# Strain_sensor.net
KiCad netlist of a schematic drawn in Altium Designer
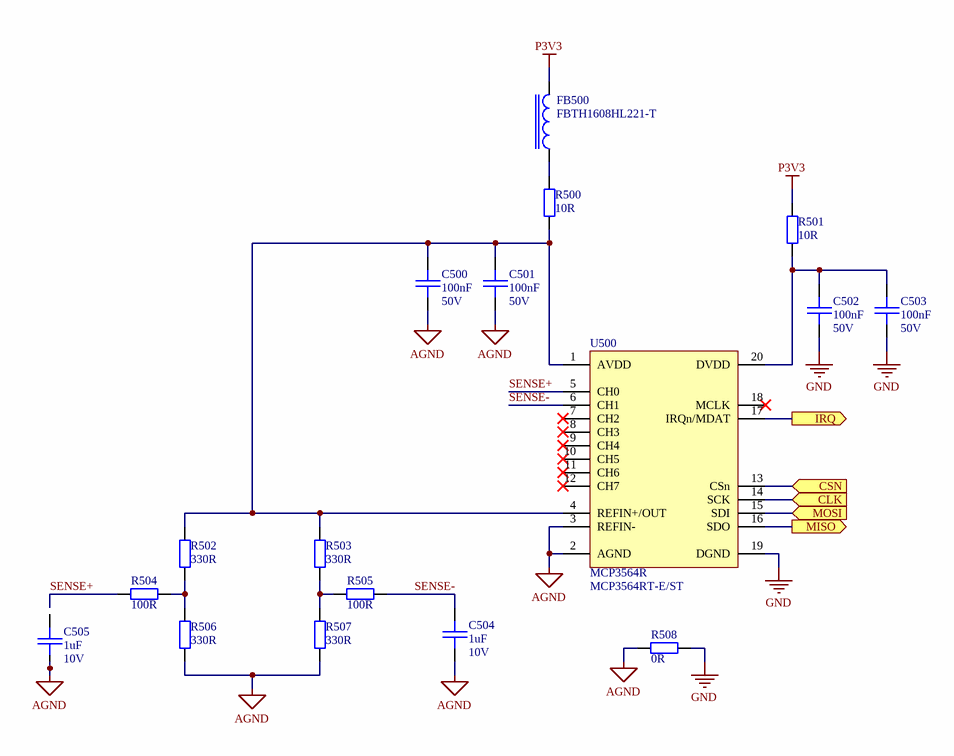
[diagram p0: Strain_sensor.SchDoc]

(export (version "E")
  (design (tool "Eeschema 10.0.6"))
  (components
    (comp (ref "C500")
      (value "100nF")
      (footprint "C0402")
      (description "General purpose ceramic capacitor")
      (fields
        (field (name "VOLTAGE") "50V")
        (field (name "MANUFACTURER") "Murata Electronics")
        (field (name "MANUFACTURER PART NO") "GRT155R71H104KE01D")
      )
      (libsource (lib "Moonlight_Library") (part "CAP"))
    )
    (comp (ref "C501")
      (value "100nF")
      (footprint "C0402")
      (description "General purpose ceramic capacitor")
      (fields
        (field (name "VOLTAGE") "50V")
        (field (name "MANUFACTURER") "Murata Electronics")
        (field (name "MANUFACTURER PART NO") "GRT155R71H104KE01D")
      )
      (libsource (lib "Moonlight_Library") (part "CAP"))
    )
    (comp (ref "C502")
      (value "100nF")
      (footprint "C0402")
      (description "General purpose ceramic capacitor")
      (fields
        (field (name "VOLTAGE") "50V")
        (field (name "MANUFACTURER") "Murata Electronics")
        (field (name "MANUFACTURER PART NO") "GRT155R71H104KE01D")
      )
      (libsource (lib "Moonlight_Library") (part "CAP"))
    )
    (comp (ref "C503")
      (value "100nF")
      (footprint "C0402")
      (description "General purpose ceramic capacitor")
      (fields
        (field (name "VOLTAGE") "50V")
        (field (name "MANUFACTURER") "Murata Electronics")
        (field (name "MANUFACTURER PART NO") "GRT155R71H104KE01D")
      )
      (libsource (lib "Moonlight_Library") (part "CAP"))
    )
    (comp (ref "C504")
      (value "1uF")
      (footprint "C0402")
      (description "General purpose ceramic capacitor")
      (fields
        (field (name "VOLTAGE") "10V")
        (field (name "MANUFACTURER") "Murata Electronics")
        (field (name "MANUFACTURER PART NO") "GRT155R61A105KE01D")
      )
      (libsource (lib "Moonlight_Library") (part "CAP"))
    )
    (comp (ref "C505")
      (value "1uF")
      (footprint "C0402")
      (description "General purpose ceramic capacitor")
      (fields
        (field (name "VOLTAGE") "10V")
        (field (name "MANUFACTURER") "Murata Electronics")
        (field (name "MANUFACTURER PART NO") "GRT155R61A105KE01D")
      )
      (libsource (lib "Moonlight_Library") (part "CAP"))
    )
    (comp (ref "FB500")
      (value "FBEAD")
      (footprint "0603_IND")
      (description "Ferrite bead")
      (fields
        (field (name "MANUFACTURER") "Taiyo Yuden")
        (field (name "MANUFACTURER PART NO") "FBTH1608HL221-T")
      )
      (libsource (lib "Moonlight_Library") (part "FBEAD"))
    )
    (comp (ref "R500")
      (value "10R")
      (footprint "R0603")
      (description "General purpose automotive thick film resistor")
      (fields
        (field (name "MANUFACTURER") "Vishay Dale")
        (field (name "MANUFACTURER PART NO") "CRCW060310R0JNEA")
      )
      (libsource (lib "Moonlight_Library") (part "RES"))
    )
    (comp (ref "R501")
      (value "10R")
      (footprint "R0603")
      (description "General purpose automotive thick film resistor")
      (fields
        (field (name "MANUFACTURER") "Vishay Dale")
        (field (name "MANUFACTURER PART NO") "CRCW060310R0JNEA")
      )
      (libsource (lib "Moonlight_Library") (part "RES"))
    )
    (comp (ref "R502")
      (value "330R")
      (footprint "R2512")
      (description "General purpose automotive thick film resistor")
      (fields
        (field (name "MANUFACTURER") "Vishay Dale")
        (field (name "MANUFACTURER PART NO") "CRCW2512330RJNEG")
      )
      (libsource (lib "Moonlight_Library") (part "RES"))
    )
    (comp (ref "R503")
      (value "330R")
      (footprint "R2512")
      (description "General purpose automotive thick film resistor")
      (fields
        (field (name "MANUFACTURER") "Vishay Dale")
        (field (name "MANUFACTURER PART NO") "CRCW2512330RJNEG")
      )
      (libsource (lib "Moonlight_Library") (part "RES"))
    )
    (comp (ref "R504")
      (value "100R")
      (footprint "R0603")
      (description "General purpose automotive thick film resistor")
      (fields
        (field (name "MANUFACTURER") "Vishay Dale")
        (field (name "MANUFACTURER PART NO") "CRCW0603100RJNEA")
      )
      (libsource (lib "") (part "RES_1"))
    )
    (comp (ref "R505")
      (value "100R")
      (footprint "R0603")
      (description "General purpose automotive thick film resistor")
      (fields
        (field (name "MANUFACTURER") "Vishay Dale")
        (field (name "MANUFACTURER PART NO") "CRCW0603100RJNEA")
      )
      (libsource (lib "") (part "RES_1"))
    )
    (comp (ref "R506")
      (value "330R")
      (footprint "R2512")
      (description "General purpose automotive thick film resistor")
      (fields
        (field (name "MANUFACTURER") "Vishay Dale")
        (field (name "MANUFACTURER PART NO") "CRCW2512330RJNEG")
      )
      (libsource (lib "Moonlight_Library") (part "RES"))
    )
    (comp (ref "R507")
      (value "330R")
      (footprint "R2512")
      (description "General purpose automotive thick film resistor")
      (fields
        (field (name "MANUFACTURER") "Vishay Dale")
        (field (name "MANUFACTURER PART NO") "CRCW2512330RJNEG")
      )
      (libsource (lib "Moonlight_Library") (part "RES"))
    )
    (comp (ref "R508")
      (value "0R")
      (footprint "R0402")
      (description "General purpose resistor")
      (fields (field (name "MANUFACTURER PART NO") "Generic resistor") (field (name "Comment") "RES"))
      (libsource (lib "") (part "RES_1"))
    )
    (comp (ref "U500")
      (value "MCP3564R")
      (footprint "20-TSSOP")
      (description "Low-noise 24-bit Delta-Sigma ADC, 2/4/8 ch single ended, 1/2/4 ch differential")
      (fields
        (field (name "MANUFACTURER PART NO") "MCP3564RT-E/ST")
        (field (name "MANUFACTURER") "Microchip Technology")
      )
      (libsource (lib "Moonlight_Library") (part "MCP3564R"))
    )
  )
  (nets
    (net (code "1") (name "/CLK") (class "Default")
      (node (ref "U500") (pin "14") (pinfunction "SCK_14") (pintype "passive"))
    )
    (net (code "2") (name "/CSN") (class "Default")
      (node (ref "U500") (pin "13") (pinfunction "CSn_13") (pintype "passive"))
    )
    (net (code "3") (name "/IRQ") (class "Default")
      (node (ref "U500") (pin "17") (pinfunction "IRQn/MDAT_17") (pintype "passive"))
    )
    (net (code "4") (name "/MISO") (class "Default")
      (node (ref "U500") (pin "16") (pinfunction "SDO_16") (pintype "passive"))
    )
    (net (code "5") (name "/MOSI") (class "Default")
      (node (ref "U500") (pin "15") (pinfunction "SDI_15") (pintype "passive"))
    )
    (net (code "6") (name "/SENSE+") (class "Default")
      (node (ref "R504") (pin "1") (pintype "passive"))
      (node (ref "U500") (pin "5") (pinfunction "CH0_5") (pintype "passive"))
    )
    (net (code "7") (name "/SENSE-") (class "Default")
      (node (ref "C504") (pin "1") (pinfunction "1_1") (pintype "passive"))
      (node (ref "R505") (pin "2") (pintype "passive"))
      (node (ref "U500") (pin "6") (pinfunction "CH1_6") (pintype "passive"))
    )
    (net (code "8") (name "AGND") (class "Default")
      (node (ref "C500") (pin "2") (pinfunction "2_2") (pintype "passive"))
      (node (ref "C501") (pin "2") (pinfunction "2_2") (pintype "passive"))
      (node (ref "C504") (pin "2") (pinfunction "2_2") (pintype "passive"))
      (node (ref "C505") (pin "2") (pinfunction "2_2") (pintype "passive"))
      (node (ref "R506") (pin "1") (pintype "passive"))
      (node (ref "R507") (pin "1") (pintype "passive"))
      (node (ref "R508") (pin "1") (pintype "passive"))
      (node (ref "U500") (pin "2") (pinfunction "AGND_2") (pintype "passive"))
      (node (ref "U500") (pin "3") (pinfunction "REFIN-_3") (pintype "passive"))
    )
    (net (code "9") (name "GND") (class "Default")
      (node (ref "C502") (pin "2") (pinfunction "2_2") (pintype "passive"))
      (node (ref "C503") (pin "2") (pinfunction "2_2") (pintype "passive"))
      (node (ref "R508") (pin "2") (pintype "passive"))
      (node (ref "U500") (pin "19") (pinfunction "DGND_19") (pintype "passive"))
    )
    (net (code "10") (name "Net-(FB500-Pad1)") (class "Default")
      (node (ref "FB500") (pin "1") (pinfunction "1_1") (pintype "passive"))
      (node (ref "R500") (pin "2") (pintype "passive"))
    )
    (net (code "11") (name "Net-(R502-Pad1)") (class "Default")
      (node (ref "R502") (pin "1") (pintype "passive"))
      (node (ref "R504") (pin "2") (pintype "passive"))
      (node (ref "R506") (pin "2") (pintype "passive"))
    )
    (net (code "12") (name "Net-(R503-Pad1)") (class "Default")
      (node (ref "R503") (pin "1") (pintype "passive"))
      (node (ref "R505") (pin "1") (pintype "passive"))
      (node (ref "R507") (pin "2") (pintype "passive"))
    )
    (net (code "13") (name "Net-(U500-AVDD)") (class "Default")
      (node (ref "C500") (pin "1") (pinfunction "1_1") (pintype "passive"))
      (node (ref "C501") (pin "1") (pinfunction "1_1") (pintype "passive"))
      (node (ref "R500") (pin "1") (pintype "passive"))
      (node (ref "R502") (pin "2") (pintype "passive"))
      (node (ref "R503") (pin "2") (pintype "passive"))
      (node (ref "U500") (pin "1") (pinfunction "AVDD_1") (pintype "passive"))
      (node (ref "U500") (pin "4") (pinfunction "REFIN+/OUT_4") (pintype "passive"))
    )
    (net (code "14") (name "Net-(U500-DVDD)") (class "Default")
      (node (ref "C502") (pin "1") (pinfunction "1_1") (pintype "passive"))
      (node (ref "C503") (pin "1") (pinfunction "1_1") (pintype "passive"))
      (node (ref "R501") (pin "1") (pintype "passive"))
      (node (ref "U500") (pin "20") (pinfunction "DVDD_20") (pintype "passive"))
    )
    (net (code "15") (name "P3V3") (class "Default")
      (node (ref "FB500") (pin "2") (pinfunction "2_2") (pintype "passive"))
      (node (ref "R501") (pin "2") (pintype "passive"))
    )
    (net (code "16") (name "unconnected-(C505-Pad1)") (class "Default")
      (node (ref "C505") (pin "1") (pinfunction "1_1") (pintype "passive"))
    )
    (net (code "17") (name "unconnected-(U500-CH2-Pad7)") (class "Default")
      (node (ref "U500") (pin "7") (pinfunction "CH2_7") (pintype "passive+no_connect"))
    )
    (net (code "18") (name "unconnected-(U500-CH3-Pad8)") (class "Default")
      (node (ref "U500") (pin "8") (pinfunction "CH3_8") (pintype "passive+no_connect"))
    )
    (net (code "19") (name "unconnected-(U500-CH4-Pad9)") (class "Default")
      (node (ref "U500") (pin "9") (pinfunction "CH4_9") (pintype "passive+no_connect"))
    )
    (net (code "20") (name "unconnected-(U500-CH5-Pad10)") (class "Default")
      (node (ref "U500") (pin "10") (pinfunction "CH5_10") (pintype "passive+no_connect"))
    )
    (net (code "21") (name "unconnected-(U500-CH6-Pad11)") (class "Default")
      (node (ref "U500") (pin "11") (pinfunction "CH6_11") (pintype "passive+no_connect"))
    )
    (net (code "22") (name "unconnected-(U500-CH7-Pad12)") (class "Default")
      (node (ref "U500") (pin "12") (pinfunction "CH7_12") (pintype "passive+no_connect"))
    )
    (net (code "23") (name "unconnected-(U500-MCLK-Pad18)") (class "Default")
      (node (ref "U500") (pin "18") (pinfunction "MCLK_18") (pintype "passive+no_connect"))
    )
  )
)
